# Sheet0-mcu.net
KiCad netlist of a schematic drawn in Altium Designer
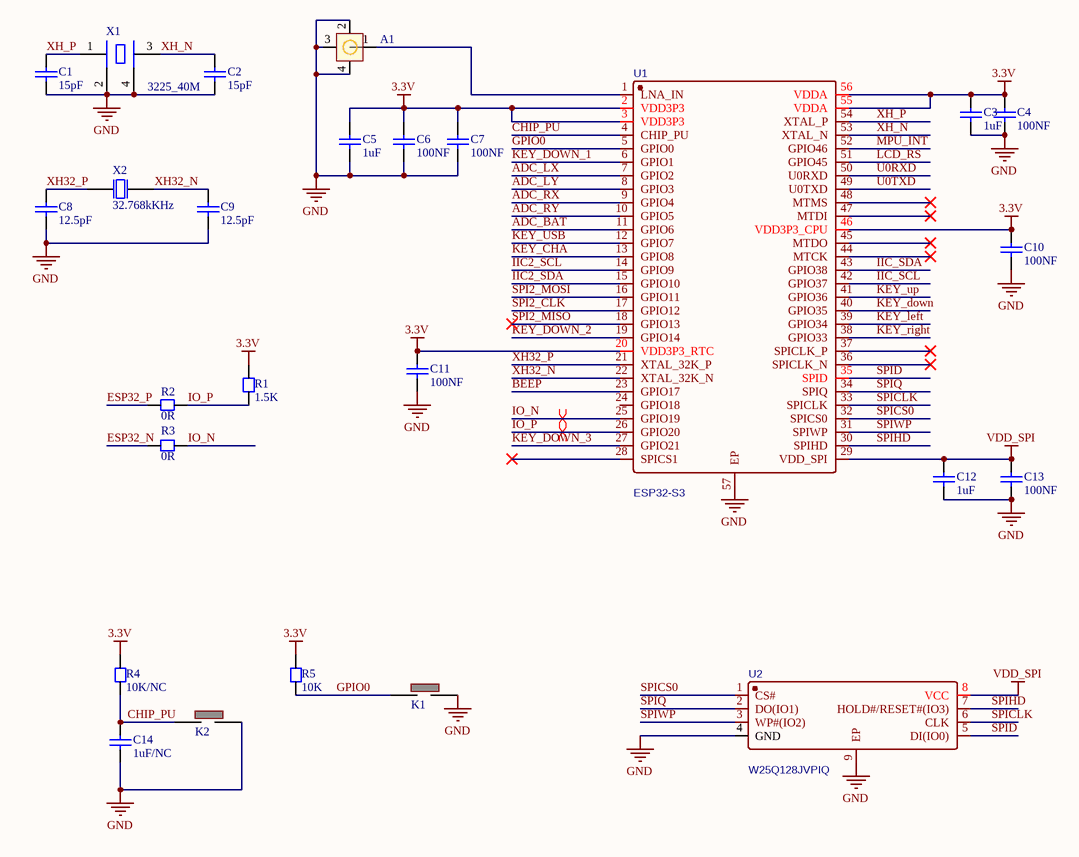
[diagram p0: Sheet0-mcu.SchDoc]

(export (version "E")
  (design (tool "Eeschema 10.0.6"))
  (components
    (comp (ref "A1")
      (value "ANT-IPEX")
      (footprint "IPEX-SMD_HC-RF-IPEX0303-01")
      (description "贴片封装的天线 封装类型为IPEX")
      (libsource (lib "antenna") (part "ANT-IPEX"))
    )
    (comp (ref "C1")
      (value "15pF")
      (footprint "CC1608-0603")
      (description "0603封装的电容")
      (fields (field (name "PUBLISHER") "Altium Limited"))
      (libsource (lib "base") (part "Cap Chip 0603"))
    )
    (comp (ref "C2")
      (value "15pF")
      (footprint "CC1608-0603")
      (description "0603封装的电容")
      (fields (field (name "PUBLISHER") "Altium Limited"))
      (libsource (lib "base") (part "Cap Chip 0603"))
    )
    (comp (ref "C3")
      (value "1uF")
      (footprint "CC1608-0603")
      (description "0603封装的电容")
      (fields (field (name "PUBLISHER") "Altium Limited"))
      (libsource (lib "base") (part "Cap Chip 0603"))
    )
    (comp (ref "C4")
      (value "100NF")
      (footprint "CC1608-0603")
      (description "0603封装的电容")
      (fields (field (name "PUBLISHER") "Altium Limited"))
      (libsource (lib "base") (part "Cap Chip 0603"))
    )
    (comp (ref "C5")
      (value "1uF")
      (footprint "CC1608-0603")
      (description "0603封装的电容")
      (fields (field (name "PUBLISHER") "Altium Limited"))
      (libsource (lib "base") (part "Cap Chip 0603"))
    )
    (comp (ref "C6")
      (value "100NF")
      (footprint "CC1608-0603")
      (description "0603封装的电容")
      (fields (field (name "PUBLISHER") "Altium Limited"))
      (libsource (lib "base") (part "Cap Chip 0603"))
    )
    (comp (ref "C7")
      (value "100NF")
      (footprint "CC1608-0603")
      (description "0603封装的电容")
      (fields (field (name "PUBLISHER") "Altium Limited"))
      (libsource (lib "base") (part "Cap Chip 0603"))
    )
    (comp (ref "C8")
      (value "12.5pF")
      (footprint "CC1608-0603")
      (description "0603封装的电容")
      (fields (field (name "PUBLISHER") "Altium Limited"))
      (libsource (lib "base") (part "Cap Chip 0603"))
    )
    (comp (ref "C9")
      (value "12.5pF")
      (footprint "CC1608-0603")
      (description "0603封装的电容")
      (fields (field (name "PUBLISHER") "Altium Limited"))
      (libsource (lib "base") (part "Cap Chip 0603"))
    )
    (comp (ref "C10")
      (value "100NF")
      (footprint "CC1608-0603")
      (description "0603封装的电容")
      (fields (field (name "PUBLISHER") "Altium Limited"))
      (libsource (lib "base") (part "Cap Chip 0603"))
    )
    (comp (ref "C11")
      (value "100NF")
      (footprint "CC1608-0603")
      (description "0603封装的电容")
      (fields (field (name "PUBLISHER") "Altium Limited"))
      (libsource (lib "base") (part "Cap Chip 0603"))
    )
    (comp (ref "C12")
      (value "1uF")
      (footprint "CC1608-0603")
      (description "0603封装的电容")
      (fields (field (name "PUBLISHER") "Altium Limited"))
      (libsource (lib "base") (part "Cap Chip 0603"))
    )
    (comp (ref "C13")
      (value "100NF")
      (footprint "CC1608-0603")
      (description "0603封装的电容")
      (fields (field (name "PUBLISHER") "Altium Limited"))
      (libsource (lib "base") (part "Cap Chip 0603"))
    )
    (comp (ref "C14")
      (value "1uF/NC")
      (footprint "CC1608-0603")
      (description "0603封装的电容")
      (fields (field (name "PUBLISHER") "Altium Limited"))
      (libsource (lib "base") (part "Cap Chip 0603"))
    )
    (comp (ref "K1")
      (value "KEY 3*4")
      (footprint "KEY 3*4")
      (description "轻触开关按键")
      (libsource (lib "base") (part "KEY 3*4"))
    )
    (comp (ref "K2")
      (value "KEY 3*4")
      (footprint "KEY 3*4")
      (description "轻触开关按键")
      (libsource (lib "base") (part "KEY 3*4"))
    )
    (comp (ref "R1")
      (value "1.5K")
      (footprint "CR1608-0603")
      (description "0603封装电阻")
      (fields (field (name "PUBLISHER") "Altium Limited"))
      (libsource (lib "") (part "Resistor Chip 0603_2"))
    )
    (comp (ref "R2")
      (value "0R")
      (footprint "CR1608-0603")
      (description "0603封装电阻")
      (fields (field (name "PUBLISHER") "Altium Limited"))
      (libsource (lib "") (part "Resistor Chip 0603_1"))
    )
    (comp (ref "R3")
      (value "0R")
      (footprint "CR1608-0603")
      (description "0603封装电阻")
      (fields (field (name "PUBLISHER") "Altium Limited"))
      (libsource (lib "") (part "Resistor Chip 0603_1"))
    )
    (comp (ref "R4")
      (value "10K/NC")
      (footprint "CR1608-0603")
      (description "0603封装电阻")
      (fields (field (name "PUBLISHER") "Altium Limited"))
      (libsource (lib "base") (part "Resistor Chip 0603"))
    )
    (comp (ref "R5")
      (value "10K")
      (footprint "CR1608-0603")
      (description "0603封装电阻")
      (fields (field (name "PUBLISHER") "Altium Limited"))
      (libsource (lib "base") (part "Resistor Chip 0603"))
    )
    (comp (ref "U1")
      (value "ESP32-S3")
      (footprint "QFN-56")
      (fields (field (name "MANUFACTURER") "ESPRESSIF(乐鑫)") (field (name "CONTRIBUTOR") "LCSC"))
      (libsource (lib "singlechip") (part "ESP32-S3"))
    )
    (comp (ref "U2")
      (value "W25Q128JVPIQ")
      (footprint "WSON-8")
      (fields (field (name "MANUFACTURER") "WINBOND(华邦)") (field (name "CONTRIBUTOR") "LCSC"))
      (libsource (lib "PB-Chip") (part "W25Q128JVPIQ"))
    )
    (comp (ref "X1")
      (value "3225_40M")
      (footprint "XTAL-3225")
      (description "3225封装的晶振")
      (libsource (lib "base") (part "XTAL 3225"))
    )
    (comp (ref "X2")
      (value "32.768kKHz")
      (footprint "XTAL-3215")
      (description "3215封装的时钟晶振")
      (libsource (lib "base") (part "XTAL 3215 32.768kKHz"))
    )
  )
  (nets
    (net (code "1") (name "/ADC_BAT") (class "Default")
      (node (ref "U1") (pin "11") (pinfunction "GPIO6_11") (pintype "passive"))
    )
    (net (code "2") (name "/ADC_LX") (class "Default")
      (node (ref "U1") (pin "7") (pinfunction "GPIO2_7") (pintype "passive"))
    )
    (net (code "3") (name "/ADC_LY") (class "Default")
      (node (ref "U1") (pin "8") (pinfunction "GPIO3_8") (pintype "passive"))
    )
    (net (code "4") (name "/ADC_RX") (class "Default")
      (node (ref "U1") (pin "9") (pinfunction "GPIO4_9") (pintype "passive"))
    )
    (net (code "5") (name "/ADC_RY") (class "Default")
      (node (ref "U1") (pin "10") (pinfunction "GPIO5_10") (pintype "passive"))
    )
    (net (code "6") (name "/BEEP") (class "Default")
      (node (ref "U1") (pin "23") (pinfunction "GPIO17_23") (pintype "passive"))
    )
    (net (code "7") (name "/CHIP_PU") (class "Default")
      (node (ref "C14") (pin "2") (pinfunction "2_2") (pintype "passive"))
      (node (ref "K2") (pin "1") (pinfunction "1_1") (pintype "passive"))
      (node (ref "R4") (pin "1") (pinfunction "1_1") (pintype "passive"))
      (node (ref "U1") (pin "4") (pinfunction "CHIP_PU_4") (pintype "passive"))
    )
    (net (code "8") (name "/ESP32_N") (class "Default")
      (node (ref "R3") (pin "2") (pinfunction "2_2") (pintype "passive"))
    )
    (net (code "9") (name "/ESP32_P") (class "Default")
      (node (ref "R2") (pin "2") (pinfunction "2_2") (pintype "passive"))
    )
    (net (code "10") (name "/GPIO0") (class "Default")
      (node (ref "K1") (pin "1") (pinfunction "1_1") (pintype "passive"))
      (node (ref "R5") (pin "1") (pinfunction "1_1") (pintype "passive"))
      (node (ref "U1") (pin "5") (pinfunction "GPIO0_5") (pintype "passive"))
    )
    (net (code "11") (name "/IIC2_SCL") (class "Default")
      (node (ref "U1") (pin "14") (pinfunction "GPIO9_14") (pintype "passive"))
    )
    (net (code "12") (name "/IIC2_SDA") (class "Default")
      (node (ref "U1") (pin "15") (pinfunction "GPIO10_15") (pintype "passive"))
    )
    (net (code "13") (name "/IIC_SCL") (class "Default")
      (node (ref "U1") (pin "42") (pinfunction "GPIO37_42") (pintype "passive"))
    )
    (net (code "14") (name "/IIC_SDA") (class "Default")
      (node (ref "U1") (pin "43") (pinfunction "GPIO38_43") (pintype "passive"))
    )
    (net (code "15") (name "/IO_N") (class "Default")
      (node (ref "R3") (pin "1") (pinfunction "1_1") (pintype "passive"))
      (node (ref "U1") (pin "25") (pinfunction "GPIO19_25") (pintype "passive"))
    )
    (net (code "16") (name "/IO_P") (class "Default")
      (node (ref "R1") (pin "2") (pinfunction "2_2") (pintype "passive"))
      (node (ref "R2") (pin "1") (pinfunction "1_1") (pintype "passive"))
      (node (ref "U1") (pin "26") (pinfunction "GPIO20_26") (pintype "passive"))
    )
    (net (code "17") (name "/KEY_CHA") (class "Default")
      (node (ref "U1") (pin "13") (pinfunction "GPIO8_13") (pintype "passive"))
    )
    (net (code "18") (name "/KEY_DOWN_1") (class "Default")
      (node (ref "U1") (pin "6") (pinfunction "GPIO1_6") (pintype "passive"))
    )
    (net (code "19") (name "/KEY_DOWN_2") (class "Default")
      (node (ref "U1") (pin "19") (pinfunction "GPIO14_19") (pintype "passive"))
    )
    (net (code "20") (name "/KEY_DOWN_3") (class "Default")
      (node (ref "U1") (pin "27") (pinfunction "GPIO21_27") (pintype "passive"))
    )
    (net (code "21") (name "/KEY_USB") (class "Default")
      (node (ref "U1") (pin "12") (pinfunction "GPIO7_12") (pintype "passive"))
    )
    (net (code "22") (name "/KEY_down") (class "Default")
      (node (ref "U1") (pin "40") (pinfunction "GPIO35_40") (pintype "passive"))
    )
    (net (code "23") (name "/KEY_left") (class "Default")
      (node (ref "U1") (pin "39") (pinfunction "GPIO34_39") (pintype "passive"))
    )
    (net (code "24") (name "/KEY_right") (class "Default")
      (node (ref "U1") (pin "38") (pinfunction "GPIO33_38") (pintype "passive"))
    )
    (net (code "25") (name "/KEY_up") (class "Default")
      (node (ref "U1") (pin "41") (pinfunction "GPIO36_41") (pintype "passive"))
    )
    (net (code "26") (name "/LCD_RS") (class "Default")
      (node (ref "U1") (pin "51") (pinfunction "GPIO45_51") (pintype "passive"))
    )
    (net (code "27") (name "/MPU_INT") (class "Default")
      (node (ref "U1") (pin "52") (pinfunction "GPIO46_52") (pintype "passive"))
    )
    (net (code "28") (name "/SPI2_CLK") (class "Default")
      (node (ref "U1") (pin "17") (pinfunction "GPIO12_17") (pintype "passive"))
    )
    (net (code "29") (name "/SPI2_MISO") (class "Default")
      (node (ref "U1") (pin "18") (pinfunction "GPIO13_18") (pintype "passive+no_connect"))
    )
    (net (code "30") (name "/SPI2_MOSI") (class "Default")
      (node (ref "U1") (pin "16") (pinfunction "GPIO11_16") (pintype "passive"))
    )
    (net (code "31") (name "/SPICLK") (class "Default")
      (node (ref "U1") (pin "33") (pinfunction "SPICLK_33") (pintype "passive"))
      (node (ref "U2") (pin "6") (pinfunction "CLK_6") (pintype "passive"))
    )
    (net (code "32") (name "/SPICS0") (class "Default")
      (node (ref "U1") (pin "32") (pinfunction "SPICS0_32") (pintype "passive"))
      (node (ref "U2") (pin "1") (pinfunction "CS#_1") (pintype "passive"))
    )
    (net (code "33") (name "/SPID") (class "Default")
      (node (ref "U1") (pin "35") (pinfunction "SPID_35") (pintype "passive"))
      (node (ref "U2") (pin "5") (pinfunction "DI(IO0)_5") (pintype "passive"))
    )
    (net (code "34") (name "/SPIHD") (class "Default")
      (node (ref "U1") (pin "30") (pinfunction "SPIHD_30") (pintype "passive"))
      (node (ref "U2") (pin "7") (pinfunction "HOLD#/RESET#(IO3)_7") (pintype "passive"))
    )
    (net (code "35") (name "/SPIQ") (class "Default")
      (node (ref "U1") (pin "34") (pinfunction "SPIQ_34") (pintype "passive"))
      (node (ref "U2") (pin "2") (pinfunction "DO(IO1)_2") (pintype "passive"))
    )
    (net (code "36") (name "/SPIWP") (class "Default")
      (node (ref "U1") (pin "31") (pinfunction "SPIWP_31") (pintype "passive"))
      (node (ref "U2") (pin "3") (pinfunction "WP#(IO2)_3") (pintype "passive"))
    )
    (net (code "37") (name "/U0RXD") (class "Default")
      (node (ref "U1") (pin "50") (pinfunction "U0RXD_50") (pintype "passive"))
    )
    (net (code "38") (name "/U0TXD") (class "Default")
      (node (ref "U1") (pin "49") (pinfunction "U0TXD_49") (pintype "passive"))
    )
    (net (code "39") (name "/XH32_N") (class "Default")
      (node (ref "C9") (pin "2") (pinfunction "2_2") (pintype "passive"))
      (node (ref "U1") (pin "22") (pinfunction "XTAL_32K_N_22") (pintype "passive"))
      (node (ref "X2") (pin "2") (pinfunction "OSC2_2") (pintype "passive"))
    )
    (net (code "40") (name "/XH32_P") (class "Default")
      (node (ref "C8") (pin "2") (pinfunction "2_2") (pintype "passive"))
      (node (ref "U1") (pin "21") (pinfunction "XTAL_32K_P_21") (pintype "passive"))
      (node (ref "X2") (pin "1") (pinfunction "OSC1_1") (pintype "passive"))
    )
    (net (code "41") (name "/XH_N") (class "Default")
      (node (ref "C2") (pin "2") (pinfunction "2_2") (pintype "passive"))
      (node (ref "U1") (pin "53") (pinfunction "XTAL_N_53") (pintype "passive"))
      (node (ref "X1") (pin "3") (pinfunction "OSC2_3") (pintype "passive"))
    )
    (net (code "42") (name "/XH_P") (class "Default")
      (node (ref "C1") (pin "2") (pinfunction "2_2") (pintype "passive"))
      (node (ref "U1") (pin "54") (pinfunction "XTAL_P_54") (pintype "passive"))
      (node (ref "X1") (pin "1") (pinfunction "OSC1_1") (pintype "passive"))
    )
    (net (code "43") (name "3.3V") (class "Default")
      (node (ref "C10") (pin "2") (pinfunction "2_2") (pintype "passive"))
      (node (ref "C11") (pin "2") (pinfunction "2_2") (pintype "passive"))
      (node (ref "C3") (pin "2") (pinfunction "2_2") (pintype "passive"))
      (node (ref "C4") (pin "2") (pinfunction "2_2") (pintype "passive"))
      (node (ref "C5") (pin "2") (pinfunction "2_2") (pintype "passive"))
      (node (ref "C6") (pin "2") (pinfunction "2_2") (pintype "passive"))
      (node (ref "C7") (pin "2") (pinfunction "2_2") (pintype "passive"))
      (node (ref "R1") (pin "1") (pinfunction "1_1") (pintype "passive"))
      (node (ref "R4") (pin "2") (pinfunction "2_2") (pintype "passive"))
      (node (ref "R5") (pin "2") (pinfunction "2_2") (pintype "passive"))
      (node (ref "U1") (pin "2") (pinfunction "VDD3P3_2") (pintype "passive"))
      (node (ref "U1") (pin "20") (pinfunction "VDD3P3_RTC_20") (pintype "passive"))
      (node (ref "U1") (pin "3") (pinfunction "VDD3P3_3") (pintype "passive"))
      (node (ref "U1") (pin "46") (pinfunction "VDD3P3_CPU_46") (pintype "passive"))
      (node (ref "U1") (pin "55") (pinfunction "VDDA_55") (pintype "passive"))
      (node (ref "U1") (pin "56") (pinfunction "VDDA_56") (pintype "passive"))
    )
    (net (code "44") (name "GND") (class "Default")
      (node (ref "A1") (pin "2") (pinfunction "2_2") (pintype "passive"))
      (node (ref "A1") (pin "3") (pinfunction "3_3") (pintype "passive"))
      (node (ref "A1") (pin "4") (pinfunction "4_4") (pintype "passive"))
      (node (ref "C1") (pin "1") (pinfunction "1_1") (pintype "passive"))
      (node (ref "C10") (pin "1") (pinfunction "1_1") (pintype "passive"))
      (node (ref "C11") (pin "1") (pinfunction "1_1") (pintype "passive"))
      (node (ref "C12") (pin "1") (pinfunction "1_1") (pintype "passive"))
      (node (ref "C13") (pin "1") (pinfunction "1_1") (pintype "passive"))
      (node (ref "C14") (pin "1") (pinfunction "1_1") (pintype "passive"))
      (node (ref "C2") (pin "1") (pinfunction "1_1") (pintype "passive"))
      (node (ref "C3") (pin "1") (pinfunction "1_1") (pintype "passive"))
      (node (ref "C4") (pin "1") (pinfunction "1_1") (pintype "passive"))
      (node (ref "C5") (pin "1") (pinfunction "1_1") (pintype "passive"))
      (node (ref "C6") (pin "1") (pinfunction "1_1") (pintype "passive"))
      (node (ref "C7") (pin "1") (pinfunction "1_1") (pintype "passive"))
      (node (ref "C8") (pin "1") (pinfunction "1_1") (pintype "passive"))
      (node (ref "C9") (pin "1") (pinfunction "1_1") (pintype "passive"))
      (node (ref "K1") (pin "2") (pinfunction "2_2") (pintype "passive"))
      (node (ref "K2") (pin "2") (pinfunction "2_2") (pintype "passive"))
      (node (ref "U1") (pin "57") (pinfunction "EP_57") (pintype "passive"))
      (node (ref "U2") (pin "4") (pinfunction "GND_4") (pintype "passive"))
      (node (ref "U2") (pin "9") (pinfunction "EP_9") (pintype "passive"))
      (node (ref "X1") (pin "2") (pinfunction "GND_2") (pintype "passive"))
      (node (ref "X1") (pin "4") (pinfunction "GND_4") (pintype "passive"))
    )
    (net (code "45") (name "Net-(U1-LNA_IN)") (class "Default")
      (node (ref "A1") (pin "1") (pinfunction "1_1") (pintype "passive"))
      (node (ref "U1") (pin "1") (pinfunction "LNA_IN_1") (pintype "passive"))
    )
    (net (code "46") (name "VDD_SPI") (class "Default")
      (node (ref "C12") (pin "2") (pinfunction "2_2") (pintype "passive"))
      (node (ref "C13") (pin "2") (pinfunction "2_2") (pintype "passive"))
      (node (ref "U1") (pin "29") (pinfunction "VDD_SPI_29") (pintype "passive"))
      (node (ref "U2") (pin "8") (pinfunction "VCC_8") (pintype "passive"))
    )
    (net (code "47") (name "unconnected-(U1-GPIO18-Pad24)") (class "Default")
      (node (ref "U1") (pin "24") (pinfunction "GPIO18_24") (pintype "passive"))
    )
    (net (code "48") (name "unconnected-(U1-MTCK-Pad44)") (class "Default")
      (node (ref "U1") (pin "44") (pinfunction "MTCK_44") (pintype "passive+no_connect"))
    )
    (net (code "49") (name "unconnected-(U1-MTDI-Pad47)") (class "Default")
      (node (ref "U1") (pin "47") (pinfunction "MTDI_47") (pintype "passive+no_connect"))
    )
    (net (code "50") (name "unconnected-(U1-MTDO-Pad45)") (class "Default")
      (node (ref "U1") (pin "45") (pinfunction "MTDO_45") (pintype "passive+no_connect"))
    )
    (net (code "51") (name "unconnected-(U1-MTMS-Pad48)") (class "Default")
      (node (ref "U1") (pin "48") (pinfunction "MTMS_48") (pintype "passive+no_connect"))
    )
    (net (code "52") (name "unconnected-(U1-SPICLK_N-Pad36)") (class "Default")
      (node (ref "U1") (pin "36") (pinfunction "SPICLK_N_36") (pintype "passive+no_connect"))
    )
    (net (code "53") (name "unconnected-(U1-SPICLK_P-Pad37)") (class "Default")
      (node (ref "U1") (pin "37") (pinfunction "SPICLK_P_37") (pintype "passive+no_connect"))
    )
    (net (code "54") (name "unconnected-(U1-SPICS1-Pad28)") (class "Default")
      (node (ref "U1") (pin "28") (pinfunction "SPICS1_28") (pintype "passive+no_connect"))
    )
  )
)
